# LazuriteMiniDongle.net
KiCad netlist of a schematic drawn in EAGLE
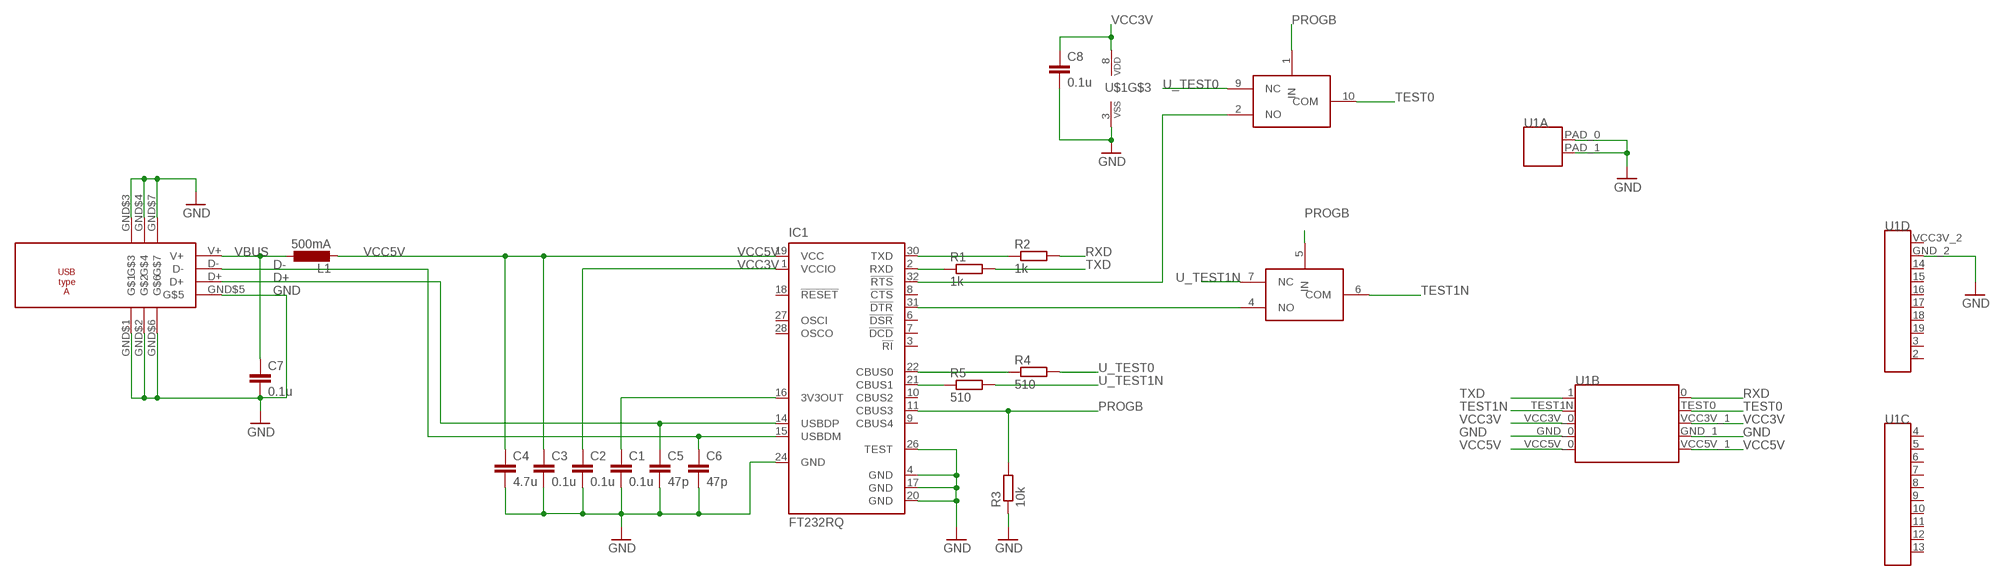
[diagram p0: schematic, sheet 1]

(export (version "E")
  (design (tool "Eeschema 10.0.6"))
  (components
    (comp (ref "C1")
      (value "0.1u")
      (footprint "eagle-import:C0402")
      (libsource (lib "eagle-import") (part "C-EUC0402"))
    )
    (comp (ref "C2")
      (value "0.1u")
      (footprint "eagle-import:C0402")
      (libsource (lib "eagle-import") (part "C-EUC0402"))
    )
    (comp (ref "C3")
      (value "0.1u")
      (footprint "eagle-import:C0402")
      (libsource (lib "eagle-import") (part "C-EUC0402"))
    )
    (comp (ref "C4")
      (value "4.7u")
      (footprint "eagle-import:C1608")
      (libsource (lib "eagle-import") (part "resistor_C-EUC1608"))
    )
    (comp (ref "C5")
      (value "47p")
      (footprint "eagle-import:C0402")
      (libsource (lib "eagle-import") (part "C-EUC0402"))
    )
    (comp (ref "C6")
      (value "47p")
      (footprint "eagle-import:C0402")
      (libsource (lib "eagle-import") (part "C-EUC0402"))
    )
    (comp (ref "C7")
      (value "0.1u")
      (footprint "eagle-import:C0402")
      (libsource (lib "eagle-import") (part "C-EUC0402"))
    )
    (comp (ref "C8")
      (value "0.1u")
      (footprint "eagle-import:C0402")
      (libsource (lib "eagle-import") (part "C-EUC0402"))
    )
    (comp (ref "IC1")
      (value "FT232RQ")
      (footprint "eagle-import:QFN32")
      (libsource (lib "eagle-import") (part "FT232RQ"))
    )
    (comp (ref "L1")
      (value "500mA")
      (footprint "eagle-import:L1812")
      (libsource (lib "eagle-import") (part "L-EUL1812"))
    )
    (comp (ref "R1")
      (value "1k")
      (footprint "eagle-import:R0402")
      (libsource (lib "eagle-import") (part "R-EU_R0402"))
    )
    (comp (ref "R2")
      (value "1k")
      (footprint "eagle-import:R0402")
      (libsource (lib "eagle-import") (part "R-EU_R0402"))
    )
    (comp (ref "R3")
      (value "10k")
      (footprint "eagle-import:R0402")
      (libsource (lib "eagle-import") (part "R-EU_R0402"))
    )
    (comp (ref "R4")
      (value "510")
      (footprint "eagle-import:R0402")
      (libsource (lib "eagle-import") (part "R-EU_R0402"))
    )
    (comp (ref "R5")
      (value "510")
      (footprint "eagle-import:R0402")
      (libsource (lib "eagle-import") (part "R-EU_R0402"))
    )
    (comp (ref "U$1")
      (value "TI-TS5A23159")
      (footprint "eagle-import:UQFN10")
      (libsource (lib "eagle-import") (part "TI-TS5A23159"))
    )
    (comp (ref "U$2")
      (value "USB-TYPE-A")
      (footprint "eagle-import:UP2-AH-TH")
      (libsource (lib "eagle-import") (part "USB-TYPE-A"))
    )
    (comp (ref "U1")
      (value "LAZURITE920JLAZURITE920J")
      (footprint "eagle-import:LAZURITE920J")
      (libsource (lib "eagle-import") (part "LAZURITE920JLAZURITE920J"))
    )
  )
  (nets
    (net (code "1") (name "/D+") (class "Default")
      (node (ref "C5") (pin "1") (pinfunction "1_1") (pintype "passive"))
      (node (ref "IC1") (pin "14") (pinfunction "USBDP_14") (pintype "bidirectional"))
      (node (ref "U$2") (pin "D+") (pinfunction "D+_D+") (pintype "bidirectional"))
    )
    (net (code "2") (name "/D-") (class "Default")
      (node (ref "C6") (pin "1") (pinfunction "1_1") (pintype "passive"))
      (node (ref "IC1") (pin "15") (pinfunction "USBDM_15") (pintype "bidirectional"))
      (node (ref "U$2") (pin "D-") (pinfunction "D-_D-") (pintype "bidirectional"))
    )
    (net (code "3") (name "/PROGB") (class "Default")
      (node (ref "IC1") (pin "11") (pinfunction "CBUS3_11") (pintype "bidirectional"))
      (node (ref "R3") (pin "2") (pinfunction "2_2") (pintype "passive"))
      (node (ref "U$1") (pin "1") (pinfunction "IN_1") (pintype "bidirectional"))
      (node (ref "U$1") (pin "5") (pinfunction "IN_5") (pintype "bidirectional"))
    )
    (net (code "4") (name "/RXD") (class "Default")
      (node (ref "R2") (pin "2") (pinfunction "2_2") (pintype "passive"))
      (node (ref "U1") (pin "0") (pinfunction "0_0") (pintype "passive"))
    )
    (net (code "5") (name "/TEST0") (class "Default")
      (node (ref "U$1") (pin "10") (pinfunction "COM_10") (pintype "bidirectional"))
      (node (ref "U1") (pin "TEST0") (pinfunction "TEST0_TEST0") (pintype "passive"))
    )
    (net (code "6") (name "/TEST1N") (class "Default")
      (node (ref "U$1") (pin "6") (pinfunction "COM_6") (pintype "bidirectional"))
      (node (ref "U1") (pin "TEST1N") (pinfunction "TEST1N_TEST1N") (pintype "passive"))
    )
    (net (code "7") (name "/TXD") (class "Default")
      (node (ref "R1") (pin "2") (pinfunction "2_2") (pintype "passive"))
      (node (ref "U1") (pin "1") (pinfunction "1_1") (pintype "passive"))
    )
    (net (code "8") (name "/U_TEST0") (class "Default")
      (node (ref "R4") (pin "2") (pinfunction "2_2") (pintype "passive"))
      (node (ref "U$1") (pin "9") (pinfunction "NC_9") (pintype "bidirectional"))
    )
    (net (code "9") (name "/U_TEST1N") (class "Default")
      (node (ref "R5") (pin "2") (pinfunction "2_2") (pintype "passive"))
      (node (ref "U$1") (pin "7") (pinfunction "NC_7") (pintype "bidirectional"))
    )
    (net (code "10") (name "/VBUS") (class "Default")
      (node (ref "C7") (pin "1") (pinfunction "1_1") (pintype "passive"))
      (node (ref "L1") (pin "1") (pinfunction "1_1") (pintype "passive"))
      (node (ref "U$2") (pin "V+") (pinfunction "V+_V+") (pintype "bidirectional"))
    )
    (net (code "11") (name "/VCC3V") (class "Default")
      (node (ref "C2") (pin "1") (pinfunction "1_1") (pintype "passive"))
      (node (ref "C8") (pin "1") (pinfunction "1_1") (pintype "passive"))
      (node (ref "IC1") (pin "1") (pinfunction "VCCIO_1") (pintype "power_in"))
      (node (ref "U$1") (pin "8") (pinfunction "VDD_8") (pintype "power_in"))
      (node (ref "U1") (pin "VCC3V_0") (pinfunction "VCC3V_0_VCC3V_0") (pintype "passive"))
      (node (ref "U1") (pin "VCC3V_1") (pinfunction "VCC3V_1_VCC3V_1") (pintype "passive"))
    )
    (net (code "12") (name "/VCC5V") (class "Default")
      (node (ref "C3") (pin "1") (pinfunction "1_1") (pintype "passive"))
      (node (ref "C4") (pin "1") (pinfunction "1_1") (pintype "passive"))
      (node (ref "IC1") (pin "19") (pinfunction "VCC_19") (pintype "power_in"))
      (node (ref "L1") (pin "2") (pinfunction "2_2") (pintype "passive"))
      (node (ref "U1") (pin "VCC5V_0") (pinfunction "VCC5V_0_VCC5V_0") (pintype "passive"))
      (node (ref "U1") (pin "VCC5V_1") (pinfunction "VCC5V_1_VCC5V_1") (pintype "passive"))
    )
    (net (code "13") (name "GND") (class "Default")
      (node (ref "C1") (pin "2") (pinfunction "2_2") (pintype "passive"))
      (node (ref "C2") (pin "2") (pinfunction "2_2") (pintype "passive"))
      (node (ref "C3") (pin "2") (pinfunction "2_2") (pintype "passive"))
      (node (ref "C4") (pin "2") (pinfunction "2_2") (pintype "passive"))
      (node (ref "C5") (pin "2") (pinfunction "2_2") (pintype "passive"))
      (node (ref "C6") (pin "2") (pinfunction "2_2") (pintype "passive"))
      (node (ref "C7") (pin "2") (pinfunction "2_2") (pintype "passive"))
      (node (ref "C8") (pin "2") (pinfunction "2_2") (pintype "passive"))
      (node (ref "IC1") (pin "17") (pinfunction "GND_17") (pintype "power_in"))
      (node (ref "IC1") (pin "20") (pinfunction "GND_20") (pintype "power_in"))
      (node (ref "IC1") (pin "24") (pinfunction "GND_24") (pintype "power_in"))
      (node (ref "IC1") (pin "26") (pinfunction "TEST_26") (pintype "input"))
      (node (ref "IC1") (pin "4") (pinfunction "GND_4") (pintype "power_in"))
      (node (ref "R3") (pin "1") (pinfunction "1_1") (pintype "passive"))
      (node (ref "U$1") (pin "3") (pinfunction "VSS_3") (pintype "power_in"))
      (node (ref "U$2") (pin "GND$1") (pinfunction "G$1_GND$1") (pintype "power_in"))
      (node (ref "U$2") (pin "GND$2") (pinfunction "G$2_GND$2") (pintype "power_in"))
      (node (ref "U$2") (pin "GND$3") (pinfunction "G$3_GND$3") (pintype "power_in"))
      (node (ref "U$2") (pin "GND$4") (pinfunction "G$4_GND$4") (pintype "power_in"))
      (node (ref "U$2") (pin "GND$5") (pinfunction "G$5_GND$5") (pintype "bidirectional"))
      (node (ref "U$2") (pin "GND$6") (pinfunction "G$6_GND$6") (pintype "power_in"))
      (node (ref "U$2") (pin "GND$7") (pinfunction "G$7_GND$7") (pintype "power_in"))
      (node (ref "U1") (pin "GND_0") (pinfunction "GND_0_GND_0") (pintype "passive"))
      (node (ref "U1") (pin "GND_1") (pinfunction "GND_1_GND_1") (pintype "passive"))
      (node (ref "U1") (pin "GND_2") (pinfunction "GND_2_GND_2") (pintype "passive"))
      (node (ref "U1") (pin "PAD_0") (pinfunction "PAD_0_PAD_0") (pintype "passive"))
      (node (ref "U1") (pin "PAD_1") (pinfunction "PAD_1_PAD_1") (pintype "passive"))
    )
    (net (code "14") (name "Net-(IC1-3V3OUT)") (class "Default")
      (node (ref "C1") (pin "1") (pinfunction "1_1") (pintype "passive"))
      (node (ref "IC1") (pin "16") (pinfunction "3V3OUT_16") (pintype "output"))
    )
    (net (code "15") (name "Net-(IC1-CBUS0)") (class "Default")
      (node (ref "IC1") (pin "22") (pinfunction "CBUS0_22") (pintype "bidirectional"))
      (node (ref "R4") (pin "1") (pinfunction "1_1") (pintype "passive"))
    )
    (net (code "16") (name "Net-(IC1-CBUS1)") (class "Default")
      (node (ref "IC1") (pin "21") (pinfunction "CBUS1_21") (pintype "bidirectional"))
      (node (ref "R5") (pin "1") (pinfunction "1_1") (pintype "passive"))
    )
    (net (code "17") (name "Net-(IC1-RXD)") (class "Default")
      (node (ref "IC1") (pin "2") (pinfunction "RXD_2") (pintype "input"))
      (node (ref "R1") (pin "1") (pinfunction "1_1") (pintype "passive"))
    )
    (net (code "18") (name "Net-(IC1-TXD)") (class "Default")
      (node (ref "IC1") (pin "30") (pinfunction "TXD_30") (pintype "output"))
      (node (ref "R2") (pin "1") (pinfunction "1_1") (pintype "passive"))
    )
    (net (code "19") (name "Net-(IC1-~{DTR})") (class "Default")
      (node (ref "IC1") (pin "31") (pinfunction "~{DTR}_31") (pintype "output"))
      (node (ref "U$1") (pin "4") (pinfunction "NO_4") (pintype "bidirectional"))
    )
    (net (code "20") (name "Net-(IC1-~{RTS})") (class "Default")
      (node (ref "IC1") (pin "32") (pinfunction "~{RTS}_32") (pintype "output"))
      (node (ref "U$1") (pin "2") (pinfunction "NO_2") (pintype "bidirectional"))
    )
    (net (code "21") (name "unconnected-(IC1-CBUS2-Pad10)") (class "Default")
      (node (ref "IC1") (pin "10") (pinfunction "CBUS2_10") (pintype "bidirectional"))
    )
    (net (code "22") (name "unconnected-(IC1-CBUS4-Pad9)") (class "Default")
      (node (ref "IC1") (pin "9") (pinfunction "CBUS4_9") (pintype "bidirectional"))
    )
    (net (code "23") (name "unconnected-(IC1-OSCI-Pad27)") (class "Default")
      (node (ref "IC1") (pin "27") (pinfunction "OSCI_27") (pintype "input"))
    )
    (net (code "24") (name "unconnected-(IC1-OSCO-Pad28)") (class "Default")
      (node (ref "IC1") (pin "28") (pinfunction "OSCO_28") (pintype "output"))
    )
    (net (code "25") (name "unconnected-(IC1-~{CTS}-Pad8)") (class "Default")
      (node (ref "IC1") (pin "8") (pinfunction "~{CTS}_8") (pintype "input"))
    )
    (net (code "26") (name "unconnected-(IC1-~{DCD}-Pad7)") (class "Default")
      (node (ref "IC1") (pin "7") (pinfunction "~{DCD}_7") (pintype "input"))
    )
    (net (code "27") (name "unconnected-(IC1-~{DSR}-Pad6)") (class "Default")
      (node (ref "IC1") (pin "6") (pinfunction "~{DSR}_6") (pintype "input"))
    )
    (net (code "28") (name "unconnected-(IC1-~{RESET}-Pad18)") (class "Default")
      (node (ref "IC1") (pin "18") (pinfunction "~{RESET}_18") (pintype "input"))
    )
    (net (code "29") (name "unconnected-(IC1-~{RI}-Pad3)") (class "Default")
      (node (ref "IC1") (pin "3") (pinfunction "~{RI}_3") (pintype "input"))
    )
    (net (code "30") (name "unconnected-(U1-Pad2)") (class "Default")
      (node (ref "U1") (pin "2") (pinfunction "2_2") (pintype "passive"))
    )
    (net (code "31") (name "unconnected-(U1-Pad3)") (class "Default")
      (node (ref "U1") (pin "3") (pinfunction "3_3") (pintype "passive"))
    )
    (net (code "32") (name "unconnected-(U1-Pad4)") (class "Default")
      (node (ref "U1") (pin "4") (pinfunction "4_4") (pintype "passive"))
    )
    (net (code "33") (name "unconnected-(U1-Pad5)") (class "Default")
      (node (ref "U1") (pin "5") (pinfunction "5_5") (pintype "passive"))
    )
    (net (code "34") (name "unconnected-(U1-Pad6)") (class "Default")
      (node (ref "U1") (pin "6") (pinfunction "6_6") (pintype "passive"))
    )
    (net (code "35") (name "unconnected-(U1-Pad7)") (class "Default")
      (node (ref "U1") (pin "7") (pinfunction "7_7") (pintype "passive"))
    )
    (net (code "36") (name "unconnected-(U1-Pad8)") (class "Default")
      (node (ref "U1") (pin "8") (pinfunction "8_8") (pintype "passive"))
    )
    (net (code "37") (name "unconnected-(U1-Pad9)") (class "Default")
      (node (ref "U1") (pin "9") (pinfunction "9_9") (pintype "passive"))
    )
    (net (code "38") (name "unconnected-(U1-Pad10)") (class "Default")
      (node (ref "U1") (pin "10") (pinfunction "10_10") (pintype "passive"))
    )
    (net (code "39") (name "unconnected-(U1-Pad11)") (class "Default")
      (node (ref "U1") (pin "11") (pinfunction "11_11") (pintype "passive"))
    )
    (net (code "40") (name "unconnected-(U1-Pad12)") (class "Default")
      (node (ref "U1") (pin "12") (pinfunction "12_12") (pintype "passive"))
    )
    (net (code "41") (name "unconnected-(U1-Pad13)") (class "Default")
      (node (ref "U1") (pin "13") (pinfunction "13_13") (pintype "passive"))
    )
    (net (code "42") (name "unconnected-(U1-Pad14)") (class "Default")
      (node (ref "U1") (pin "14") (pinfunction "14_14") (pintype "passive"))
    )
    (net (code "43") (name "unconnected-(U1-Pad15)") (class "Default")
      (node (ref "U1") (pin "15") (pinfunction "15_15") (pintype "passive"))
    )
    (net (code "44") (name "unconnected-(U1-Pad16)") (class "Default")
      (node (ref "U1") (pin "16") (pinfunction "16_16") (pintype "passive"))
    )
    (net (code "45") (name "unconnected-(U1-Pad17)") (class "Default")
      (node (ref "U1") (pin "17") (pinfunction "17_17") (pintype "passive"))
    )
    (net (code "46") (name "unconnected-(U1-Pad18)") (class "Default")
      (node (ref "U1") (pin "18") (pinfunction "18_18") (pintype "passive"))
    )
    (net (code "47") (name "unconnected-(U1-Pad19)") (class "Default")
      (node (ref "U1") (pin "19") (pinfunction "19_19") (pintype "passive"))
    )
    (net (code "48") (name "unconnected-(U1-PadVCC3V_2)") (class "Default")
      (node (ref "U1") (pin "VCC3V_2") (pinfunction "VCC3V_2_VCC3V_2") (pintype "passive"))
    )
  )
)
